# Sheet_2.net
KiCad netlist of a schematic drawn in Altium Designer
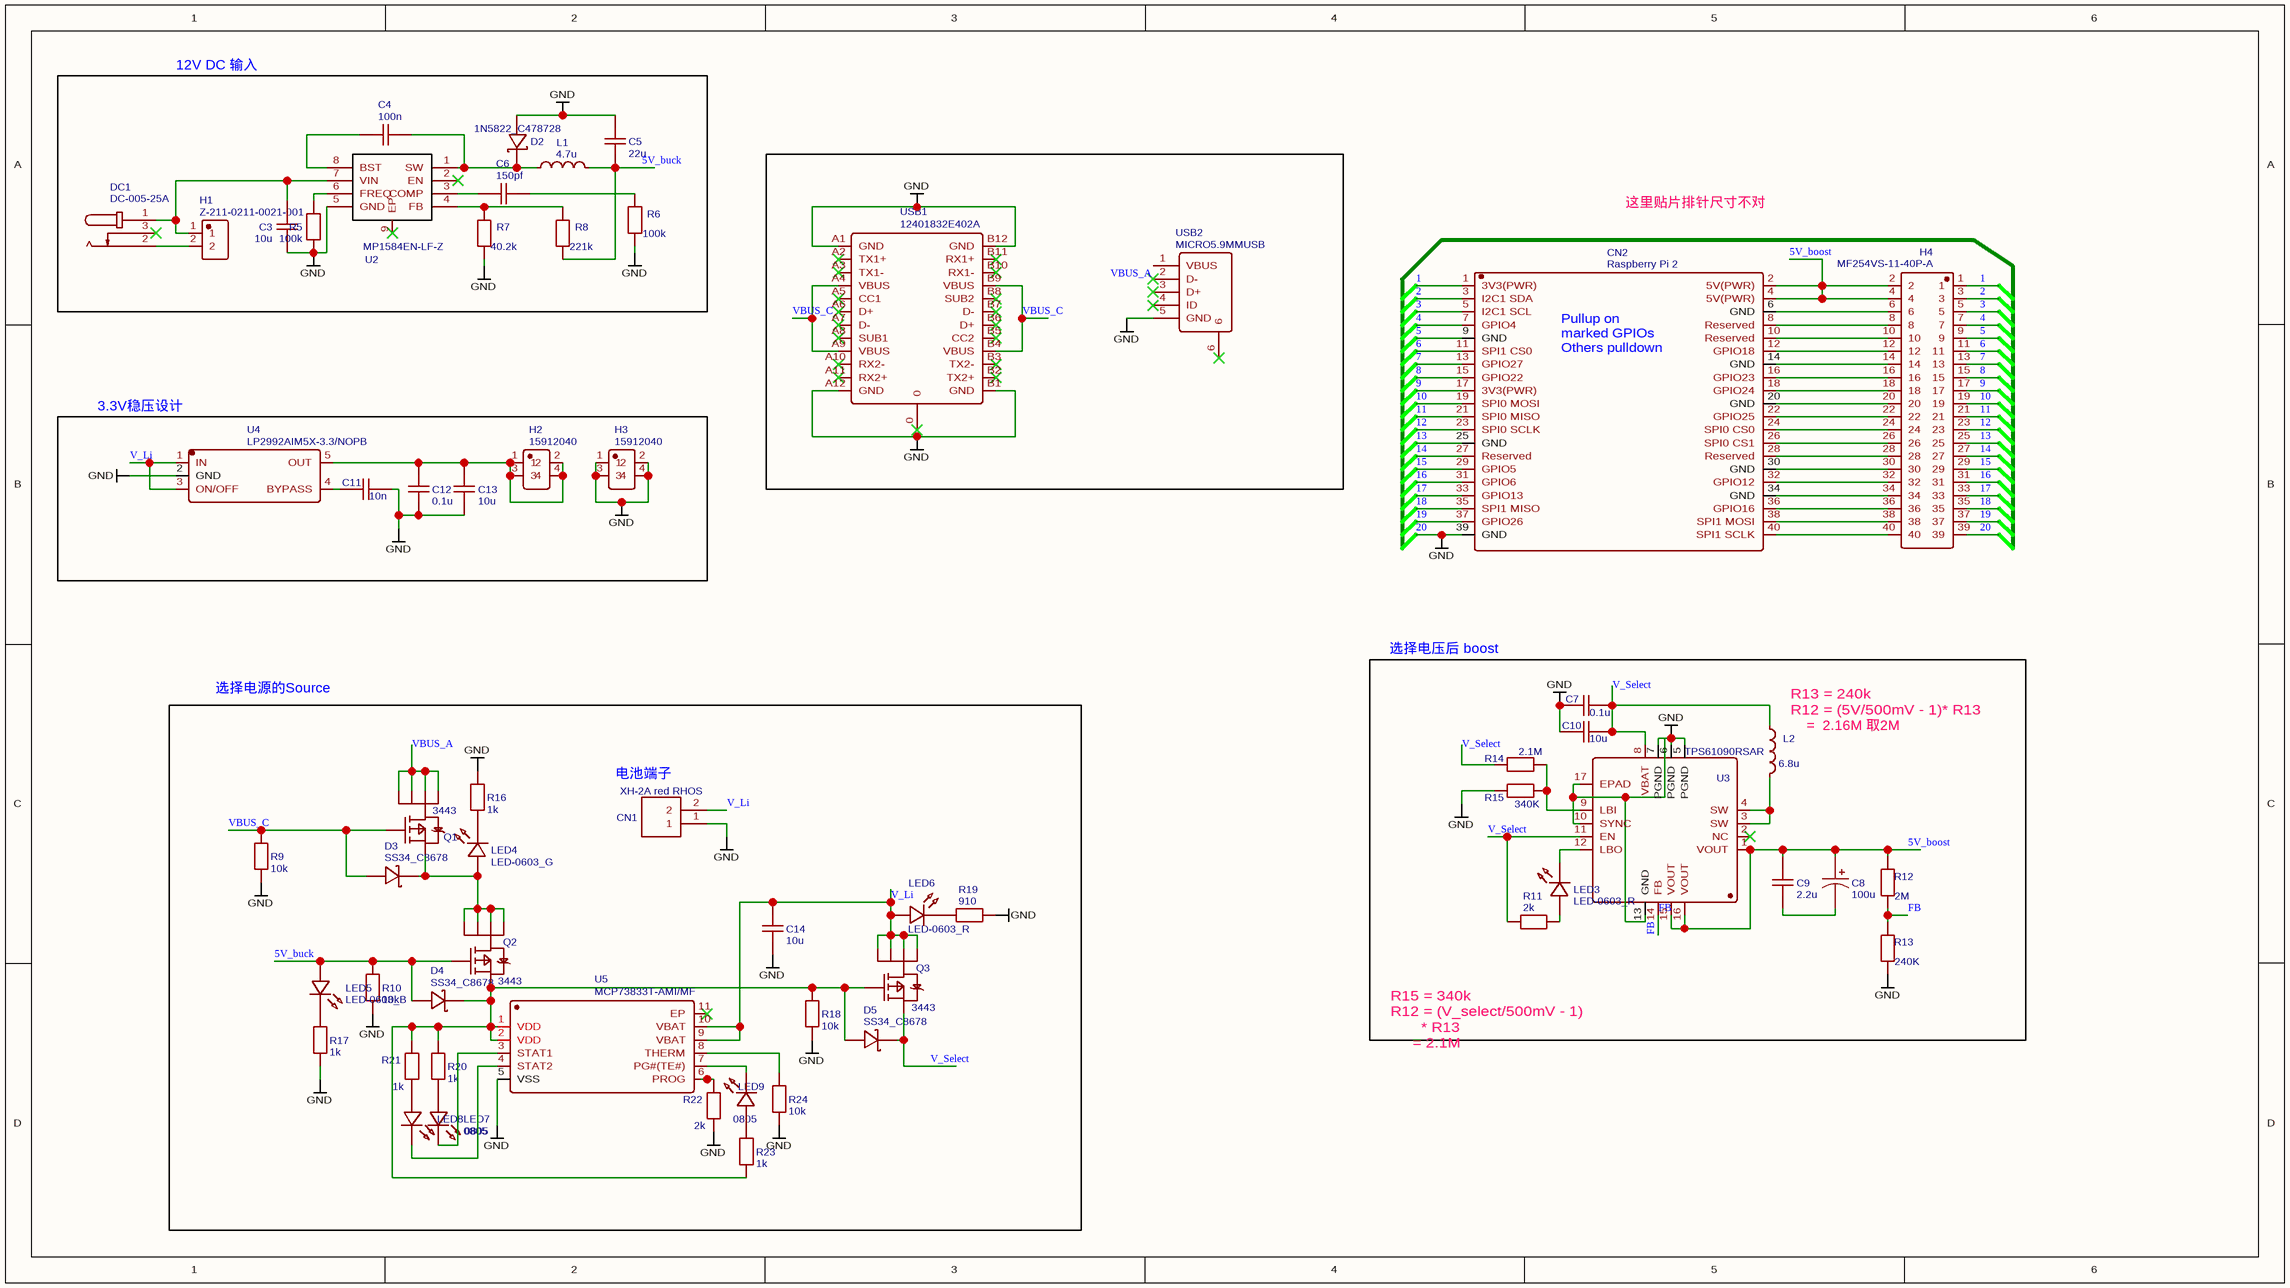
[diagram p0: Sheet_2.schdoc]

(export (version "E")
  (design (tool "Eeschema 10.0.6"))
  (components
    (comp (ref "C3")
      (value "10u")
      (fields (field (name "CONTRIBUTOR") "LCEDA_Lib"))
      (libsource (lib "altium-import") (part "root_1_10u_"))
    )
    (comp (ref "C4")
      (value "100n")
      (fields (field (name "CONTRIBUTOR") "LCEDA_Lib"))
      (libsource (lib "altium-import") (part "root_2_100n_"))
    )
    (comp (ref "C5")
      (value "22u")
      (fields (field (name "CONTRIBUTOR") "LCEDA_Lib"))
      (libsource (lib "altium-import") (part "root_3_22u_"))
    )
    (comp (ref "C6")
      (value "150pf")
      (fields (field (name "CONTRIBUTOR") "LCEDA_Lib"))
      (libsource (lib "altium-import") (part "root_0_150pf_"))
    )
    (comp (ref "C7")
      (value "0.1u")
      (fields (field (name "CONTRIBUTOR") "LCEDA_Lib"))
      (libsource (lib "altium-import") (part "root_2_0.1u_"))
    )
    (comp (ref "C8")
      (value "100u")
      (fields (field (name "CONTRIBUTOR") "LCEDA_Lib"))
      (libsource (lib "altium-import") (part "root_3_100u_"))
    )
    (comp (ref "C9")
      (value "2.2u")
      (fields (field (name "CONTRIBUTOR") "LCEDA_Lib"))
      (libsource (lib "altium-import") (part "root_1_2.2u_"))
    )
    (comp (ref "C10")
      (value "10u")
      (fields (field (name "CONTRIBUTOR") "LCEDA_Lib"))
      (libsource (lib "altium-import") (part "root_2_10u_"))
    )
    (comp (ref "C11")
      (value "10n")
      (fields (field (name "CONTRIBUTOR") "LCEDA_Lib"))
      (libsource (lib "altium-import") (part "root_2_10n_"))
    )
    (comp (ref "C12")
      (value "0.1u")
      (fields (field (name "CONTRIBUTOR") "LCEDA_Lib"))
      (libsource (lib "altium-import") (part "root_3_0.1u_"))
    )
    (comp (ref "C13")
      (value "10u")
      (fields (field (name "CONTRIBUTOR") "LCEDA_Lib"))
      (libsource (lib "altium-import") (part "root_3_10u_"))
    )
    (comp (ref "C14")
      (value "10u")
      (fields (field (name "CONTRIBUTOR") "LCEDA_Lib"))
      (libsource (lib "") (part "root_1_10u__1"))
    )
    (comp (ref "CN1")
      (value "XH-2A red RHOS")
      (fields (field (name "BOM_SUPPLIER PART") "C24192"))
      (libsource (lib "altium-import") (part "root_2_XH-2A red RHOS_"))
    )
    (comp (ref "CN2")
      (value "Raspberry Pi 2")
      (fields (field (name "CONTRIBUTOR") "Jason+Pierce"))
      (libsource (lib "altium-import") (part "root_0_Raspberry Pi 2_"))
    )
    (comp (ref "D2")
      (value "1N5822_C478728")
      (fields
        (field (name "BOM_SUPPLIER PART") "C478728")
        (field (name "BOM_MANUFACTURER PART") "1N5822")
        (field (name "CONTRIBUTOR") "LCSC")
      )
      (libsource (lib "altium-import") (part "root_1_1N5822_C478728_"))
    )
    (comp (ref "D3")
      (value "SS34_C8678")
      (fields (field (name "BOM_MANUFACTURER PART") "SS34") (field (name "BOM_SUPPLIER PART") "C8678"))
      (libsource (lib "altium-import") (part "root_2_SS34_C8678_"))
    )
    (comp (ref "D4")
      (value "SS34_C8678")
      (fields (field (name "BOM_MANUFACTURER PART") "SS34") (field (name "BOM_SUPPLIER PART") "C8678"))
      (libsource (lib "altium-import") (part "root_2_SS34_C8678_"))
    )
    (comp (ref "D5")
      (value "SS34_C8678")
      (fields (field (name "BOM_MANUFACTURER PART") "SS34") (field (name "BOM_SUPPLIER PART") "C8678"))
      (libsource (lib "altium-import") (part "root_2_SS34_C8678_"))
    )
    (comp (ref "DC1")
      (value "DC-005-25A")
      (fields (field (name "BOM_SUPPLIER PART") "C136715") (field (name "CONTRIBUTOR") "LCSC"))
      (libsource (lib "altium-import") (part "root_0_DC-005-25A_"))
    )
    (comp (ref "H1")
      (value "Z-211-0211-0021-001")
      (fields (field (name "BOM_SUPPLIER PART") "C152154") (field (name "CONTRIBUTOR") "LCSC"))
      (libsource (lib "altium-import") (part "root_0_Z-211-0211-0021-001_"))
    )
    (comp (ref "H2")
      (value "15912040")
      (fields (field (name "BOM_SUPPLIER PART") "C586564") (field (name "CONTRIBUTOR") "LCSC"))
      (libsource (lib "altium-import") (part "root_0_15912040_"))
    )
    (comp (ref "H3")
      (value "15912040")
      (fields (field (name "BOM_SUPPLIER PART") "C586564") (field (name "CONTRIBUTOR") "LCSC"))
      (libsource (lib "altium-import") (part "root_0_15912040_"))
    )
    (comp (ref "H4")
      (value "MF254VS-11-40P-A")
      (fields (field (name "BOM_SUPPLIER PART") "C492236") (field (name "CONTRIBUTOR") "LCSC"))
      (libsource (lib "altium-import") (part "root_0_MF254VS-11-40P-A_"))
    )
    (comp (ref "L1")
      (value "4.7u")
      (fields (field (name "CONTRIBUTOR") "LCEDA_Lib"))
      (libsource (lib "altium-import") (part "root_0_4.7u_"))
    )
    (comp (ref "L2")
      (value "6.8u")
      (fields (field (name "CONTRIBUTOR") "LCEDA_Lib"))
      (libsource (lib "altium-import") (part "root_3_6.8u_"))
    )
    (comp (ref "LED3")
      (value "LED-0603_R")
      (fields
        (field (name "BOM_MANUFACTURER PART") "19-217/R6C-AL1M2VY/3T")
        (field (name "BOM_SUPPLIER PART") "C72044")
        (field (name "CONTRIBUTOR") "LCEDA_01")
      )
      (libsource (lib "altium-import") (part "root_1_LED-0603_R_"))
    )
    (comp (ref "LED4")
      (value "LED-0603_G")
      (fields
        (field (name "BOM_MANUFACTURER PART") "19-217/GHC-YR1S2/3T")
        (field (name "BOM_SUPPLIER PART") "C72043")
        (field (name "CONTRIBUTOR") "LCEDA_Lib")
      )
      (libsource (lib "altium-import") (part "root_1_LED-0603_G_"))
    )
    (comp (ref "LED5")
      (value "LED-0603_B")
      (fields
        (field (name "BOM_MANUFACTURER PART") "19-217/BHC-ZL1M2RY/3T")
        (field (name "BOM_SUPPLIER PART") "C72041")
        (field (name "CONTRIBUTOR") "LCEDA_01")
      )
      (libsource (lib "altium-import") (part "root_3_LED-0603_B_"))
    )
    (comp (ref "LED6")
      (value "LED-0603_R")
      (fields
        (field (name "BOM_MANUFACTURER PART") "19-217/R6C-AL1M2VY/3T")
        (field (name "BOM_SUPPLIER PART") "C72044")
        (field (name "CONTRIBUTOR") "LCEDA_01")
      )
      (libsource (lib "altium-import") (part "root_0_LED-0603_R_"))
    )
    (comp (ref "LED7")
      (value "0805")
      (fields
        (field (name "BOM_MANUFACTURER PART") "17-21SURC/S530-A3/TR8")
        (field (name "BOM_SUPPLIER PART") "C72037")
        (field (name "CONTRIBUTOR") "LCEDA_Lib")
      )
      (libsource (lib "altium-import") (part "root_3_0805_"))
    )
    (comp (ref "LED8")
      (value "0805")
      (fields
        (field (name "BOM_MANUFACTURER PART") "NCD0805G1")
        (field (name "BOM_SUPPLIER PART") "C84260")
        (field (name "CONTRIBUTOR") "LCEDA_Lib")
      )
      (libsource (lib "altium-import") (part "root_3_0805_"))
    )
    (comp (ref "LED9")
      (value "0805")
      (fields
        (field (name "BOM_MANUFACTURER PART") "D-B080508B1-KS2")
        (field (name "BOM_SUPPLIER PART") "C108412")
        (field (name "CONTRIBUTOR") "LCEDA_Lib")
      )
      (libsource (lib "altium-import") (part "root_1_0805_"))
    )
    (comp (ref "Q1")
      (value "3443")
      (fields
        (field (name "BOM_SUPPLIER PART") "C558216")
        (field (name "BOM_MANUFACTURER PART") "NTGS3443T1G")
        (field (name "CONTRIBUTOR") "LCSC")
      )
      (libsource (lib "altium-import") (part "root_2_3443_"))
    )
    (comp (ref "Q2")
      (value "3443")
      (fields
        (field (name "BOM_SUPPLIER PART") "C558216")
        (field (name "BOM_MANUFACTURER PART") "NTGS3443T1G")
        (field (name "CONTRIBUTOR") "LCSC")
      )
      (libsource (lib "altium-import") (part "root_2_3443_"))
    )
    (comp (ref "Q3")
      (value "3443")
      (fields
        (field (name "BOM_SUPPLIER PART") "C558216")
        (field (name "BOM_MANUFACTURER PART") "NTGS3443T1G")
        (field (name "CONTRIBUTOR") "LCSC")
      )
      (libsource (lib "altium-import") (part "root_2_3443_"))
    )
    (comp (ref "R5")
      (value "100k")
      (fields (field (name "CONTRIBUTOR") "LCEDA_Lib"))
      (libsource (lib "altium-import") (part "root_3_100k_"))
    )
    (comp (ref "R6")
      (value "100k")
      (fields (field (name "CONTRIBUTOR") "LCEDA_Lib"))
      (libsource (lib "altium-import") (part "root_3_100k_"))
    )
    (comp (ref "R7")
      (value "40.2k")
      (fields (field (name "CONTRIBUTOR") "LCEDA_Lib"))
      (libsource (lib "altium-import") (part "root_3_40.2k_"))
    )
    (comp (ref "R8")
      (value "221k")
      (fields (field (name "CONTRIBUTOR") "LCEDA_Lib"))
      (libsource (lib "altium-import") (part "root_3_221k_"))
    )
    (comp (ref "R9")
      (value "10k")
      (fields (field (name "CONTRIBUTOR") "LCEDA_Lib"))
      (libsource (lib "altium-import") (part "root_1_10k_"))
    )
    (comp (ref "R10")
      (value "10k")
      (fields (field (name "CONTRIBUTOR") "LCEDA_Lib"))
      (libsource (lib "altium-import") (part "root_1_10k_"))
    )
    (comp (ref "R11")
      (value "2k")
      (fields (field (name "CONTRIBUTOR") "LCEDA_Lib"))
      (libsource (lib "altium-import") (part "root_2_2k_"))
    )
    (comp (ref "R12")
      (value "2M")
      (fields (field (name "CONTRIBUTOR") "LCEDA_Lib"))
      (libsource (lib "altium-import") (part "root_3_2M_"))
    )
    (comp (ref "R13")
      (value "240K")
      (fields (field (name "CONTRIBUTOR") "LCEDA_Lib"))
      (libsource (lib "altium-import") (part "root_3_240K_"))
    )
    (comp (ref "R14")
      (value "2.1M")
      (fields (field (name "CONTRIBUTOR") "LCEDA_Lib"))
      (libsource (lib "altium-import") (part "root_2_2.1M_"))
    )
    (comp (ref "R15")
      (value "340K")
      (fields (field (name "CONTRIBUTOR") "LCEDA_Lib"))
      (libsource (lib "altium-import") (part "root_2_340K_"))
    )
    (comp (ref "R16")
      (value "1k")
      (fields (field (name "CONTRIBUTOR") "LCEDA_Lib"))
      (libsource (lib "altium-import") (part "root_1_1k_"))
    )
    (comp (ref "R17")
      (value "1k")
      (fields (field (name "CONTRIBUTOR") "LCEDA_Lib"))
      (libsource (lib "altium-import") (part "root_1_1k_"))
    )
    (comp (ref "R18")
      (value "10k")
      (fields (field (name "CONTRIBUTOR") "LCEDA_Lib"))
      (libsource (lib "altium-import") (part "root_1_10k_"))
    )
    (comp (ref "R19")
      (value "910")
      (fields (field (name "CONTRIBUTOR") "LCEDA_Lib"))
      (libsource (lib "altium-import") (part "root_2_910_"))
    )
    (comp (ref "R20")
      (value "1k")
      (fields (field (name "CONTRIBUTOR") "LCEDA_Lib"))
      (libsource (lib "altium-import") (part "root_1_1k_"))
    )
    (comp (ref "R21")
      (value "1k")
      (fields (field (name "CONTRIBUTOR") "LCEDA_Lib"))
      (libsource (lib "altium-import") (part "root_1_1k_"))
    )
    (comp (ref "R22")
      (value "2k")
      (fields (field (name "CONTRIBUTOR") "LCEDA_Lib"))
      (libsource (lib "altium-import") (part "root_1_2k_"))
    )
    (comp (ref "R23")
      (value "1k")
      (fields (field (name "CONTRIBUTOR") "LCEDA_Lib"))
      (libsource (lib "altium-import") (part "root_1_1k_"))
    )
    (comp (ref "R24")
      (value "10k")
      (fields (field (name "CONTRIBUTOR") "LCEDA_Lib"))
      (libsource (lib "altium-import") (part "root_1_10k_"))
    )
    (comp (ref "U2")
      (value "MP1584EN-LF-Z")
      (fields (field (name "BOM_SUPPLIER PART") "C15051"))
      (libsource (lib "altium-import") (part "root_0_MP1584EN-LF-Z_"))
    )
    (comp (ref "U3")
      (value "TPS61090RSAR")
      (fields (field (name "BOM_SUPPLIER PART") "C206167") (field (name "CONTRIBUTOR") "LCSC"))
      (libsource (lib "altium-import") (part "root_2_TPS61090RSAR_"))
    )
    (comp (ref "U4")
      (value "LP2992AIM5X-3.3/NOPB")
      (fields (field (name "BOM_SUPPLIER PART") "C111076") (field (name "CONTRIBUTOR") "LCSC"))
      (libsource (lib "altium-import") (part "root_0_LP2992AIM5X-3.3/NOPB_"))
    )
    (comp (ref "U5")
      (value "MCP73833T-AMI/MF")
      (fields (field (name "BOM_SUPPLIER PART") "C340160") (field (name "CONTRIBUTOR") "LCSC"))
      (libsource (lib "altium-import") (part "root_0_MCP73833T-AMI/MF_"))
    )
    (comp (ref "USB1")
      (value "12401832E402A")
      (fields (field (name "BOM_SUPPLIER PART") "C464604") (field (name "CONTRIBUTOR") "LCSC"))
      (libsource (lib "altium-import") (part "root_0_12401832E402A_"))
    )
    (comp (ref "USB2")
      (value "MICRO5.9MMUSB")
      (fields
        (field (name "BOM_SUPPLIER PART") "C393940")
        (field (name "BOM_MANUFACTURER PART") "MICRO5.9mmusb")
        (field (name "CONTRIBUTOR") "LCSC")
      )
      (libsource (lib "altium-import") (part "root_0_MICRO5.9MMUSB_"))
    )
  )
  (nets
    (net (code "1") (name "/1") (class "Default")
      (node (ref "CN2") (pin "1") (pinfunction "3V3(PWR)_1") (pintype "passive"))
      (node (ref "H4") (pin "1") (pinfunction "1_1") (pintype "passive"))
    )
    (net (code "2") (name "/2") (class "Default")
      (node (ref "CN2") (pin "3") (pinfunction "I2C1_SDA_3") (pintype "passive"))
      (node (ref "H4") (pin "3") (pinfunction "3_3") (pintype "passive"))
    )
    (net (code "3") (name "/3") (class "Default")
      (node (ref "CN2") (pin "5") (pinfunction "I2C1_SCL_5") (pintype "passive"))
      (node (ref "H4") (pin "5") (pinfunction "5_5") (pintype "passive"))
    )
    (net (code "4") (name "/4") (class "Default")
      (node (ref "CN2") (pin "7") (pinfunction "GPIO4_7") (pintype "passive"))
      (node (ref "H4") (pin "7") (pinfunction "7_7") (pintype "passive"))
    )
    (net (code "5") (name "/5") (class "Default")
      (node (ref "CN2") (pin "9") (pinfunction "GND_9") (pintype "passive"))
      (node (ref "H4") (pin "9") (pinfunction "9_9") (pintype "passive"))
    )
    (net (code "6") (name "/5V_boost") (class "Default")
      (node (ref "C8") (pin "1") (pinfunction "1_1") (pintype "passive"))
      (node (ref "C9") (pin "2") (pinfunction "2_2") (pintype "passive"))
      (node (ref "CN2") (pin "2") (pinfunction "5V(PWR)_2") (pintype "passive"))
      (node (ref "CN2") (pin "4") (pinfunction "5V(PWR)_4") (pintype "passive"))
      (node (ref "H4") (pin "2") (pinfunction "2_2") (pintype "passive"))
      (node (ref "H4") (pin "4") (pinfunction "4_4") (pintype "passive"))
      (node (ref "R12") (pin "1") (pinfunction "1_1") (pintype "passive"))
      (node (ref "U3") (pin "1") (pinfunction "VOUT_1") (pintype "passive"))
      (node (ref "U3") (pin "15") (pinfunction "VOUT_15") (pintype "passive"))
      (node (ref "U3") (pin "16") (pinfunction "VOUT_16") (pintype "passive"))
    )
    (net (code "7") (name "/5V_buck") (class "Default")
      (node (ref "C5") (pin "2") (pinfunction "2_2") (pintype "passive"))
      (node (ref "D4") (pin "2") (pinfunction "A_2") (pintype "passive"))
      (node (ref "L1") (pin "2") (pinfunction "2_2") (pintype "passive"))
      (node (ref "LED5") (pin "1") (pinfunction "1_1") (pintype "passive"))
      (node (ref "Q2") (pin "3") (pinfunction "G_3") (pintype "passive"))
      (node (ref "R10") (pin "2") (pinfunction "2_2") (pintype "passive"))
      (node (ref "R8") (pin "2") (pinfunction "2_2") (pintype "passive"))
    )
    (net (code "8") (name "/6") (class "Default")
      (node (ref "CN2") (pin "11") (pinfunction "SPI1_CS0_11") (pintype "passive"))
      (node (ref "H4") (pin "11") (pinfunction "11_11") (pintype "passive"))
    )
    (net (code "9") (name "/7") (class "Default")
      (node (ref "CN2") (pin "13") (pinfunction "GPIO27_13") (pintype "passive"))
      (node (ref "H4") (pin "13") (pinfunction "13_13") (pintype "passive"))
    )
    (net (code "10") (name "/8") (class "Default")
      (node (ref "CN2") (pin "15") (pinfunction "GPIO22_15") (pintype "passive"))
      (node (ref "H4") (pin "15") (pinfunction "15_15") (pintype "passive"))
    )
    (net (code "11") (name "/9") (class "Default")
      (node (ref "CN2") (pin "17") (pinfunction "3V3(PWR)_17") (pintype "passive"))
      (node (ref "H4") (pin "17") (pinfunction "17_17") (pintype "passive"))
    )
    (net (code "12") (name "/10") (class "Default")
      (node (ref "CN2") (pin "19") (pinfunction "SPI0_MOSI_19") (pintype "passive"))
      (node (ref "H4") (pin "19") (pinfunction "19_19") (pintype "passive"))
    )
    (net (code "13") (name "/11") (class "Default")
      (node (ref "CN2") (pin "21") (pinfunction "SPI0_MISO_21") (pintype "passive"))
      (node (ref "H4") (pin "21") (pinfunction "21_21") (pintype "passive"))
    )
    (net (code "14") (name "/12") (class "Default")
      (node (ref "CN2") (pin "23") (pinfunction "SPI0_SCLK_23") (pintype "passive"))
      (node (ref "H4") (pin "23") (pinfunction "23_23") (pintype "passive"))
    )
    (net (code "15") (name "/13") (class "Default")
      (node (ref "CN2") (pin "25") (pinfunction "GND_25") (pintype "passive"))
      (node (ref "H4") (pin "25") (pinfunction "25_25") (pintype "passive"))
    )
    (net (code "16") (name "/14") (class "Default")
      (node (ref "CN2") (pin "27") (pinfunction "Reserved_27") (pintype "passive"))
      (node (ref "H4") (pin "27") (pinfunction "27_27") (pintype "passive"))
    )
    (net (code "17") (name "/15") (class "Default")
      (node (ref "CN2") (pin "29") (pinfunction "GPIO5_29") (pintype "passive"))
      (node (ref "H4") (pin "29") (pinfunction "29_29") (pintype "passive"))
    )
    (net (code "18") (name "/16") (class "Default")
      (node (ref "CN2") (pin "31") (pinfunction "GPIO6_31") (pintype "passive"))
      (node (ref "H4") (pin "31") (pinfunction "31_31") (pintype "passive"))
    )
    (net (code "19") (name "/17") (class "Default")
      (node (ref "CN2") (pin "33") (pinfunction "GPIO13_33") (pintype "passive"))
      (node (ref "H4") (pin "33") (pinfunction "33_33") (pintype "passive"))
    )
    (net (code "20") (name "/18") (class "Default")
      (node (ref "CN2") (pin "35") (pinfunction "SPI1_MISO_35") (pintype "passive"))
      (node (ref "H4") (pin "35") (pinfunction "35_35") (pintype "passive"))
    )
    (net (code "21") (name "/19") (class "Default")
      (node (ref "CN2") (pin "37") (pinfunction "GPIO26_37") (pintype "passive"))
      (node (ref "H4") (pin "37") (pinfunction "37_37") (pintype "passive"))
    )
    (net (code "22") (name "/FB") (class "Default")
      (node (ref "R12") (pin "2") (pinfunction "2_2") (pintype "passive"))
      (node (ref "R13") (pin "1") (pinfunction "1_1") (pintype "passive"))
      (node (ref "U3") (pin "14") (pinfunction "FB_14") (pintype "passive"))
    )
    (net (code "23") (name "/VBUS_A") (class "Default")
      (node (ref "Q1") (pin "1") (pinfunction "D_1") (pintype "passive"))
      (node (ref "Q1") (pin "2") (pinfunction "D_2") (pintype "passive"))
      (node (ref "Q1") (pin "5") (pinfunction "D_5") (pintype "passive"))
      (node (ref "Q1") (pin "6") (pinfunction "D_6") (pintype "passive"))
      (node (ref "USB2") (pin "1") (pinfunction "VBUS_1") (pintype "passive"))
    )
    (net (code "24") (name "/VBUS_C") (class "Default")
      (node (ref "D3") (pin "2") (pinfunction "A_2") (pintype "passive"))
      (node (ref "Q1") (pin "3") (pinfunction "G_3") (pintype "passive"))
      (node (ref "R9") (pin "2") (pinfunction "2_2") (pintype "passive"))
      (node (ref "USB1") (pin "A4") (pinfunction "VBUS_A4") (pintype "passive"))
      (node (ref "USB1") (pin "A9") (pinfunction "VBUS_A9") (pintype "passive"))
      (node (ref "USB1") (pin "B4") (pinfunction "VBUS_B4") (pintype "passive"))
      (node (ref "USB1") (pin "B9") (pinfunction "VBUS_B9") (pintype "passive"))
    )
    (net (code "25") (name "/V_Li") (class "Default")
      (node (ref "C14") (pin "2") (pinfunction "2_2") (pintype "passive"))
      (node (ref "CN1") (pin "2") (pinfunction "2_2") (pintype "passive"))
      (node (ref "LED6") (pin "1") (pinfunction "1_1") (pintype "passive"))
      (node (ref "Q3") (pin "1") (pinfunction "D_1") (pintype "passive"))
      (node (ref "Q3") (pin "2") (pinfunction "D_2") (pintype "passive"))
      (node (ref "Q3") (pin "5") (pinfunction "D_5") (pintype "passive"))
      (node (ref "Q3") (pin "6") (pinfunction "D_6") (pintype "passive"))
      (node (ref "U4") (pin "1") (pinfunction "IN_1") (pintype "passive"))
      (node (ref "U4") (pin "3") (pinfunction "ON/OFF_3") (pintype "passive"))
      (node (ref "U5") (pin "10") (pinfunction "VBAT_10") (pintype "passive"))
      (node (ref "U5") (pin "9") (pinfunction "VBAT_9") (pintype "passive"))
    )
    (net (code "26") (name "/V_Select") (class "Default")
      (node (ref "C10") (pin "1") (pinfunction "1_1") (pintype "passive"))
      (node (ref "C7") (pin "1") (pinfunction "1_1") (pintype "passive"))
      (node (ref "D5") (pin "1") (pinfunction "K_1") (pintype "passive"))
      (node (ref "L2") (pin "1") (pinfunction "1_1") (pintype "passive"))
      (node (ref "Q3") (pin "4") (pinfunction "S_4") (pintype "passive"))
      (node (ref "R11") (pin "2") (pinfunction "2_2") (pintype "passive"))
      (node (ref "R14") (pin "2") (pinfunction "2_2") (pintype "passive"))
      (node (ref "U3") (pin "11") (pinfunction "EN_11") (pintype "passive"))
      (node (ref "U3") (pin "8") (pinfunction "VBAT_8") (pintype "passive"))
    )
    (net (code "27") (name "GND") (class "Default")
      (node (ref "C10") (pin "2") (pinfunction "2_2") (pintype "passive"))
      (node (ref "C11") (pin "1") (pinfunction "1_1") (pintype "passive"))
      (node (ref "C12") (pin "2") (pinfunction "2_2") (pintype "passive"))
      (node (ref "C13") (pin "2") (pinfunction "2_2") (pintype "passive"))
      (node (ref "C14") (pin "1") (pinfunction "1_1") (pintype "passive"))
      (node (ref "C3") (pin "1") (pinfunction "1_1") (pintype "passive"))
      (node (ref "C5") (pin "1") (pinfunction "1_1") (pintype "passive"))
      (node (ref "C7") (pin "2") (pinfunction "2_2") (pintype "passive"))
      (node (ref "CN1") (pin "1") (pinfunction "1_1") (pintype "passive"))
      (node (ref "CN2") (pin "39") (pinfunction "GND_39") (pintype "passive"))
      (node (ref "D2") (pin "2") (pinfunction "A_2") (pintype "passive"))
      (node (ref "H3") (pin "1") (pinfunction "1_1") (pintype "passive"))
      (node (ref "H3") (pin "2") (pinfunction "2_2") (pintype "passive"))
      (node (ref "H3") (pin "3") (pinfunction "3_3") (pintype "passive"))
      (node (ref "H3") (pin "4") (pinfunction "4_4") (pintype "passive"))
      (node (ref "H4") (pin "39") (pinfunction "39_39") (pintype "passive"))
      (node (ref "R10") (pin "1") (pinfunction "1_1") (pintype "passive"))
      (node (ref "R13") (pin "2") (pinfunction "2_2") (pintype "passive"))
      (node (ref "R15") (pin "2") (pinfunction "2_2") (pintype "passive"))
      (node (ref "R16") (pin "2") (pinfunction "2_2") (pintype "passive"))
      (node (ref "R17") (pin "1") (pinfunction "1_1") (pintype "passive"))
      (node (ref "R18") (pin "1") (pinfunction "1_1") (pintype "passive"))
      (node (ref "R19") (pin "1") (pinfunction "1_1") (pintype "passive"))
      (node (ref "R22") (pin "1") (pinfunction "1_1") (pintype "passive"))
      (node (ref "R24") (pin "1") (pinfunction "1_1") (pintype "passive"))
      (node (ref "R5") (pin "2") (pinfunction "2_2") (pintype "passive"))
      (node (ref "R6") (pin "2") (pinfunction "2_2") (pintype "passive"))
      (node (ref "R7") (pin "2") (pinfunction "2_2") (pintype "passive"))
      (node (ref "R9") (pin "1") (pinfunction "1_1") (pintype "passive"))
      (node (ref "U2") (pin "5") (pinfunction "GND_5") (pintype "passive"))
      (node (ref "U3") (pin "10") (pinfunction "SYNC_10") (pintype "passive"))
      (node (ref "U3") (pin "13") (pinfunction "GND_13") (pintype "passive"))
      (node (ref "U3") (pin "17") (pinfunction "EPAD_17") (pintype "passive"))
      (node (ref "U3") (pin "5") (pinfunction "PGND_5") (pintype "passive"))
      (node (ref "U3") (pin "6") (pinfunction "PGND_6") (pintype "passive"))
      (node (ref "U3") (pin "7") (pinfunction "PGND_7") (pintype "passive"))
      (node (ref "U4") (pin "2") (pinfunction "GND_2") (pintype "passive"))
      (node (ref "U5") (pin "5") (pinfunction "VSS_5") (pintype "passive"))
      (node (ref "USB1") (pin "A1") (pinfunction "GND_A1") (pintype "passive"))
      (node (ref "USB1") (pin "A12") (pinfunction "GND_A12") (pintype "passive"))
      (node (ref "USB1") (pin "B1") (pinfunction "GND_B1") (pintype "passive"))
      (node (ref "USB1") (pin "B12") (pinfunction "GND_B12") (pintype "passive"))
      (node (ref "USB2") (pin "5") (pinfunction "GND_5") (pintype "passive"))
    )
    (net (code "28") (name "Net-(C6-Pad2)") (class "Default")
      (node (ref "C6") (pin "2") (pinfunction "2_2") (pintype "passive"))
      (node (ref "R6") (pin "1") (pinfunction "1_1") (pintype "passive"))
    )
    (net (code "29") (name "Net-(C8-Pad2)") (class "Default")
      (node (ref "C8") (pin "2") (pinfunction "2_2") (pintype "passive"))
      (node (ref "C9") (pin "1") (pinfunction "1_1") (pintype "passive"))
    )
    (net (code "30") (name "Net-(CN2-GND-Pad6)") (class "Default")
      (node (ref "CN2") (pin "6") (pinfunction "GND_6") (pintype "passive"))
      (node (ref "H4") (pin "6") (pinfunction "6_6") (pintype "passive"))
    )
    (net (code "31") (name "Net-(CN2-GND-Pad14)") (class "Default")
      (node (ref "CN2") (pin "14") (pinfunction "GND_14") (pintype "passive"))
      (node (ref "H4") (pin "14") (pinfunction "14_14") (pintype "passive"))
    )
    (net (code "32") (name "Net-(CN2-GND-Pad20)") (class "Default")
      (node (ref "CN2") (pin "20") (pinfunction "GND_20") (pintype "passive"))
      (node (ref "H4") (pin "20") (pinfunction "20_20") (pintype "passive"))
    )
    (net (code "33") (name "Net-(CN2-GND-Pad30)") (class "Default")
      (node (ref "CN2") (pin "30") (pinfunction "GND_30") (pintype "passive"))
      (node (ref "H4") (pin "30") (pinfunction "30_30") (pintype "passive"))
    )
    (net (code "34") (name "Net-(CN2-GND-Pad34)") (class "Default")
      (node (ref "CN2") (pin "34") (pinfunction "GND_34") (pintype "passive"))
      (node (ref "H4") (pin "34") (pinfunction "34_34") (pintype "passive"))
    )
    (net (code "35") (name "Net-(CN2-GPIO12)") (class "Default")
      (node (ref "CN2") (pin "32") (pinfunction "GPIO12_32") (pintype "passive"))
      (node (ref "H4") (pin "32") (pinfunction "32_32") (pintype "passive"))
    )
    (net (code "36") (name "Net-(CN2-GPIO16)") (class "Default")
      (node (ref "CN2") (pin "36") (pinfunction "GPIO16_36") (pintype "passive"))
      (node (ref "H4") (pin "36") (pinfunction "36_36") (pintype "passive"))
    )
    (net (code "37") (name "Net-(CN2-GPIO18)") (class "Default")
      (node (ref "CN2") (pin "12") (pinfunction "GPIO18_12") (pintype "passive"))
      (node (ref "H4") (pin "12") (pinfunction "12_12") (pintype "passive"))
    )
    (net (code "38") (name "Net-(CN2-GPIO23)") (class "Default")
      (node (ref "CN2") (pin "16") (pinfunction "GPIO23_16") (pintype "passive"))
      (node (ref "H4") (pin "16") (pinfunction "16_16") (pintype "passive"))
    )
    (net (code "39") (name "Net-(CN2-GPIO24)") (class "Default")
      (node (ref "CN2") (pin "18") (pinfunction "GPIO24_18") (pintype "passive"))
      (node (ref "H4") (pin "18") (pinfunction "18_18") (pintype "passive"))
    )
    (net (code "40") (name "Net-(CN2-GPIO25)") (class "Default")
      (node (ref "CN2") (pin "22") (pinfunction "GPIO25_22") (pintype "passive"))
      (node (ref "H4") (pin "22") (pinfunction "22_22") (pintype "passive"))
    )
    (net (code "41") (name "Net-(CN2-Reserved-Pad8)") (class "Default")
      (node (ref "CN2") (pin "8") (pinfunction "Reserved_8") (pintype "passive"))
      (node (ref "H4") (pin "8") (pinfunction "8_8") (pintype "passive"))
    )
    (net (code "42") (name "Net-(CN2-Reserved-Pad10)") (class "Default")
      (node (ref "CN2") (pin "10") (pinfunction "Reserved_10") (pintype "passive"))
      (node (ref "H4") (pin "10") (pinfunction "10_10") (pintype "passive"))
    )
    (net (code "43") (name "Net-(CN2-Reserved-Pad28)") (class "Default")
      (node (ref "CN2") (pin "28") (pinfunction "Reserved_28") (pintype "passive"))
      (node (ref "H4") (pin "28") (pinfunction "28_28") (pintype "passive"))
    )
    (net (code "44") (name "Net-(CN2-SPI0_CS0)") (class "Default")
      (node (ref "CN2") (pin "24") (pinfunction "SPI0_CS0_24") (pintype "passive"))
      (node (ref "H4") (pin "24") (pinfunction "24_24") (pintype "passive"))
    )
    (net (code "45") (name "Net-(CN2-SPI0_CS1)") (class "Default")
      (node (ref "CN2") (pin "26") (pinfunction "SPI0_CS1_26") (pintype "passive"))
      (node (ref "H4") (pin "26") (pinfunction "26_26") (pintype "passive"))
    )
    (net (code "46") (name "Net-(CN2-SPI1_MOSI)") (class "Default")
      (node (ref "CN2") (pin "38") (pinfunction "SPI1_MOSI_38") (pintype "passive"))
      (node (ref "H4") (pin "38") (pinfunction "38_38") (pintype "passive"))
    )
    (net (code "47") (name "Net-(CN2-SPI1_SCLK)") (class "Default")
      (node (ref "CN2") (pin "40") (pinfunction "SPI1_SCLK_40") (pintype "passive"))
      (node (ref "H4") (pin "40") (pinfunction "40_40") (pintype "passive"))
    )
    (net (code "48") (name "Net-(D2-K)") (class "Default")
      (node (ref "C4") (pin "1") (pinfunction "1_1") (pintype "passive"))
      (node (ref "D2") (pin "1") (pinfunction "K_1") (pintype "passive"))
      (node (ref "L1") (pin "1") (pinfunction "1_1") (pintype "passive"))
      (node (ref "U2") (pin "1") (pinfunction "SW_1") (pintype "passive"))
    )
    (net (code "49") (name "Net-(D3-K)") (class "Default")
      (node (ref "D3") (pin "1") (pinfunction "K_1") (pintype "passive"))
      (node (ref "LED4") (pin "1") (pinfunction "1_1") (pintype "passive"))
      (node (ref "Q1") (pin "4") (pinfunction "S_4") (pintype "passive"))
      (node (ref "Q2") (pin "1") (pinfunction "D_1") (pintype "passive"))
      (node (ref "Q2") (pin "2") (pinfunction "D_2") (pintype "passive"))
      (node (ref "Q2") (pin "5") (pinfunction "D_5") (pintype "passive"))
      (node (ref "Q2") (pin "6") (pinfunction "D_6") (pintype "passive"))
    )
    (net (code "50") (name "Net-(D4-K)") (class "Default")
      (node (ref "D4") (pin "1") (pinfunction "K_1") (pintype "passive"))
      (node (ref "D5") (pin "2") (pinfunction "A_2") (pintype "passive"))
      (node (ref "Q2") (pin "4") (pinfunction "S_4") (pintype "passive"))
      (node (ref "Q3") (pin "3") (pinfunction "G_3") (pintype "passive"))
      (node (ref "R18") (pin "2") (pinfunction "2_2") (pintype "passive"))
      (node (ref "R20") (pin "2") (pinfunction "2_2") (pintype "passive"))
      (node (ref "R21") (pin "2") (pinfunction "2_2") (pintype "passive"))
      (node (ref "R23") (pin "1") (pinfunction "1_1") (pintype "passive"))
      (node (ref "U5") (pin "1") (pinfunction "VDD_1") (pintype "passive"))
      (node (ref "U5") (pin "2") (pinfunction "VDD_2") (pintype "passive"))
    )
    (net (code "51") (name "Net-(DC1-Pad2)") (class "Default")
      (node (ref "DC1") (pin "2") (pinfunction "2_2") (pintype "passive"))
      (node (ref "H1") (pin "2") (pinfunction "2_2") (pintype "passive"))
    )
    (net (code "52") (name "Net-(L2-Pad2)") (class "Default")
      (node (ref "L2") (pin "2") (pinfunction "2_2") (pintype "passive"))
      (node (ref "U3") (pin "3") (pinfunction "SW_3") (pintype "passive"))
      (node (ref "U3") (pin "4") (pinfunction "SW_4") (pintype "passive"))
    )
    (net (code "53") (name "Net-(LED3-Pad1)") (class "Default")
      (node (ref "LED3") (pin "1") (pinfunction "1_1") (pintype "passive"))
      (node (ref "R11") (pin "1") (pinfunction "1_1") (pintype "passive"))
    )
    (net (code "54") (name "Net-(LED4-Pad2)") (class "Default")
      (node (ref "LED4") (pin "2") (pinfunction "2_2") (pintype "passive"))
      (node (ref "R16") (pin "1") (pinfunction "1_1") (pintype "passive"))
    )
    (net (code "55") (name "Net-(LED5-Pad2)") (class "Default")
      (node (ref "LED5") (pin "2") (pinfunction "2_2") (pintype "passive"))
      (node (ref "R17") (pin "2") (pinfunction "2_2") (pintype "passive"))
    )
    (net (code "56") (name "Net-(LED6-Pad2)") (class "Default")
      (node (ref "LED6") (pin "2") (pinfunction "2_2") (pintype "passive"))
      (node (ref "R19") (pin "2") (pinfunction "2_2") (pintype "passive"))
    )
    (net (code "57") (name "Net-(LED7-Pad1)") (class "Default")
      (node (ref "LED7") (pin "1") (pinfunction "1_1") (pintype "passive"))
      (node (ref "R20") (pin "1") (pinfunction "1_1") (pintype "passive"))
    )
    (net (code "58") (name "Net-(LED8-Pad1)") (class "Default")
      (node (ref "LED8") (pin "1") (pinfunction "1_1") (pintype "passive"))
      (node (ref "R21") (pin "1") (pinfunction "1_1") (pintype "passive"))
    )
    (net (code "59") (name "Net-(LED9-Pad1)") (class "Default")
      (node (ref "LED9") (pin "1") (pinfunction "1_1") (pintype "passive"))
      (node (ref "R23") (pin "2") (pinfunction "2_2") (pintype "passive"))
    )
    (net (code "60") (name "Net-(U2-BST)") (class "Default")
      (node (ref "C4") (pin "2") (pinfunction "2_2") (pintype "passive"))
      (node (ref "U2") (pin "8") (pinfunction "BST_8") (pintype "passive"))
    )
    (net (code "61") (name "Net-(U2-COMP)") (class "Default")
      (node (ref "C6") (pin "1") (pinfunction "1_1") (pintype "passive"))
      (node (ref "U2") (pin "3") (pinfunction "COMP_3") (pintype "passive"))
    )
    (net (code "62") (name "Net-(U2-FB)") (class "Default")
      (node (ref "R7") (pin "1") (pinfunction "1_1") (pintype "passive"))
      (node (ref "R8") (pin "1") (pinfunction "1_1") (pintype "passive"))
      (node (ref "U2") (pin "4") (pinfunction "FB_4") (pintype "passive"))
    )
    (net (code "63") (name "Net-(U2-FREQ)") (class "Default")
      (node (ref "R5") (pin "1") (pinfunction "1_1") (pintype "passive"))
      (node (ref "U2") (pin "6") (pinfunction "FREQ_6") (pintype "passive"))
    )
    (net (code "64") (name "Net-(U2-VIN)") (class "Default")
      (node (ref "C3") (pin "2") (pinfunction "2_2") (pintype "passive"))
      (node (ref "DC1") (pin "1") (pinfunction "1_1") (pintype "passive"))
      (node (ref "H1") (pin "1") (pinfunction "1_1") (pintype "passive"))
      (node (ref "U2") (pin "7") (pinfunction "VIN_7") (pintype "passive"))
    )
    (net (code "65") (name "Net-(U3-LBI)") (class "Default")
      (node (ref "R14") (pin "1") (pinfunction "1_1") (pintype "passive"))
      (node (ref "R15") (pin "1") (pinfunction "1_1") (pintype "passive"))
      (node (ref "U3") (pin "9") (pinfunction "LBI_9") (pintype "passive"))
    )
    (net (code "66") (name "Net-(U3-LBO)") (class "Default")
      (node (ref "LED3") (pin "2") (pinfunction "2_2") (pintype "passive"))
      (node (ref "U3") (pin "12") (pinfunction "LBO_12") (pintype "passive"))
    )
    (net (code "67") (name "Net-(U4-BYPASS)") (class "Default")
      (node (ref "C11") (pin "2") (pinfunction "2_2") (pintype "passive"))
      (node (ref "U4") (pin "4") (pinfunction "BYPASS_4") (pintype "passive"))
    )
    (net (code "68") (name "Net-(U4-OUT)") (class "Default")
      (node (ref "C12") (pin "1") (pinfunction "1_1") (pintype "passive"))
      (node (ref "C13") (pin "1") (pinfunction "1_1") (pintype "passive"))
      (node (ref "H2") (pin "1") (pinfunction "1_1") (pintype "passive"))
      (node (ref "H2") (pin "2") (pinfunction "2_2") (pintype "passive"))
      (node (ref "H2") (pin "3") (pinfunction "3_3") (pintype "passive"))
      (node (ref "H2") (pin "4") (pinfunction "4_4") (pintype "passive"))
      (node (ref "U4") (pin "5") (pinfunction "OUT_5") (pintype "passive"))
    )
    (net (code "69") (name "Net-(U5-PG#(TE#))") (class "Default")
      (node (ref "LED9") (pin "2") (pinfunction "2_2") (pintype "passive"))
      (node (ref "U5") (pin "7") (pinfunction "PG#(TE#)_7") (pintype "passive"))
    )
    (net (code "70") (name "Net-(U5-PROG)") (class "Default")
      (node (ref "R22") (pin "2") (pinfunction "2_2") (pintype "passive"))
      (node (ref "U5") (pin "6") (pinfunction "PROG_6") (pintype "passive"))
    )
    (net (code "71") (name "Net-(U5-STAT1)") (class "Default")
      (node (ref "LED7") (pin "2") (pinfunction "2_2") (pintype "passive"))
      (node (ref "U5") (pin "3") (pinfunction "STAT1_3") (pintype "passive"))
    )
    (net (code "72") (name "Net-(U5-STAT2)") (class "Default")
      (node (ref "LED8") (pin "2") (pinfunction "2_2") (pintype "passive"))
      (node (ref "U5") (pin "4") (pinfunction "STAT2_4") (pintype "passive"))
    )
    (net (code "73") (name "Net-(U5-THERM)") (class "Default")
      (node (ref "R24") (pin "2") (pinfunction "2_2") (pintype "passive"))
      (node (ref "U5") (pin "8") (pinfunction "THERM_8") (pintype "passive"))
    )
    (net (code "74") (name "unconnected-(DC1-Pad3)") (class "Default")
      (node (ref "DC1") (pin "3") (pinfunction "3_3") (pintype "passive+no_connect"))
    )
    (net (code "75") (name "unconnected-(U2-EN-Pad2)") (class "Default")
      (node (ref "U2") (pin "2") (pinfunction "EN_2") (pintype "passive+no_connect"))
    )
    (net (code "76") (name "unconnected-(U2-EP-Pad9)") (class "Default")
      (node (ref "U2") (pin "9") (pinfunction "EP_9") (pintype "passive+no_connect"))
    )
    (net (code "77") (name "unconnected-(U3-NC-Pad2)") (class "Default")
      (node (ref "U3") (pin "2") (pinfunction "NC_2") (pintype "passive+no_connect"))
    )
    (net (code "78") (name "unconnected-(U5-EP-Pad11)") (class "Default")
      (node (ref "U5") (pin "11") (pinfunction "EP_11") (pintype "passive+no_connect"))
    )
    (net (code "79") (name "unconnected-(USB1-CC1-PadA5)") (class "Default")
      (node (ref "USB1") (pin "A5") (pinfunction "CC1_A5") (pintype "passive+no_connect"))
    )
    (net (code "80") (name "unconnected-(USB1-CC2-PadB5)") (class "Default")
      (node (ref "USB1") (pin "B5") (pinfunction "CC2_B5") (pintype "passive+no_connect"))
    )
    (net (code "81") (name "unconnected-(USB1-D+-PadA6)") (class "Default")
      (node (ref "USB1") (pin "A6") (pinfunction "D+_A6") (pintype "passive+no_connect"))
    )
    (net (code "82") (name "unconnected-(USB1-D+-PadB6)") (class "Default")
      (node (ref "USB1") (pin "B6") (pinfunction "D+_B6") (pintype "passive+no_connect"))
    )
    (net (code "83") (name "unconnected-(USB1-D--PadA7)") (class "Default")
      (node (ref "USB1") (pin "A7") (pinfunction "D-_A7") (pintype "passive+no_connect"))
    )
    (net (code "84") (name "unconnected-(USB1-D--PadB7)") (class "Default")
      (node (ref "USB1") (pin "B7") (pinfunction "D-_B7") (pintype "passive+no_connect"))
    )
    (net (code "85") (name "unconnected-(USB1-Pad0)") (class "Default")
      (node (ref "USB1") (pin "0") (pinfunction "0_0") (pintype "passive+no_connect"))
    )
    (net (code "86") (name "unconnected-(USB1-RX1+-PadB11)") (class "Default")
      (node (ref "USB1") (pin "B11") (pinfunction "RX1+_B11") (pintype "passive+no_connect"))
    )
    (net (code "87") (name "unconnected-(USB1-RX1--PadB10)") (class "Default")
      (node (ref "USB1") (pin "B10") (pinfunction "RX1-_B10") (pintype "passive+no_connect"))
    )
    (net (code "88") (name "unconnected-(USB1-RX2+-PadA11)") (class "Default")
      (node (ref "USB1") (pin "A11") (pinfunction "RX2+_A11") (pintype "passive+no_connect"))
    )
    (net (code "89") (name "unconnected-(USB1-RX2--PadA10)") (class "Default")
      (node (ref "USB1") (pin "A10") (pinfunction "RX2-_A10") (pintype "passive+no_connect"))
    )
    (net (code "90") (name "unconnected-(USB1-SUB1-PadA8)") (class "Default")
      (node (ref "USB1") (pin "A8") (pinfunction "SUB1_A8") (pintype "passive+no_connect"))
    )
    (net (code "91") (name "unconnected-(USB1-SUB2-PadB8)") (class "Default")
      (node (ref "USB1") (pin "B8") (pinfunction "SUB2_B8") (pintype "passive+no_connect"))
    )
    (net (code "92") (name "unconnected-(USB1-TX1+-PadA2)") (class "Default")
      (node (ref "USB1") (pin "A2") (pinfunction "TX1+_A2") (pintype "passive+no_connect"))
    )
    (net (code "93") (name "unconnected-(USB1-TX1--PadA3)") (class "Default")
      (node (ref "USB1") (pin "A3") (pinfunction "TX1-_A3") (pintype "passive+no_connect"))
    )
    (net (code "94") (name "unconnected-(USB1-TX2+-PadB2)") (class "Default")
      (node (ref "USB1") (pin "B2") (pinfunction "TX2+_B2") (pintype "passive+no_connect"))
    )
    (net (code "95") (name "unconnected-(USB1-TX2--PadB3)") (class "Default")
      (node (ref "USB1") (pin "B3") (pinfunction "TX2-_B3") (pintype "passive+no_connect"))
    )
    (net (code "96") (name "unconnected-(USB2-D+-Pad3)") (class "Default")
      (node (ref "USB2") (pin "3") (pinfunction "D+_3") (pintype "passive+no_connect"))
    )
    (net (code "97") (name "unconnected-(USB2-D--Pad2)") (class "Default")
      (node (ref "USB2") (pin "2") (pinfunction "D-_2") (pintype "passive+no_connect"))
    )
    (net (code "98") (name "unconnected-(USB2-ID-Pad4)") (class "Default")
      (node (ref "USB2") (pin "4") (pinfunction "ID_4") (pintype "passive+no_connect"))
    )
    (net (code "99") (name "unconnected-(USB2-Pad6)") (class "Default")
      (node (ref "USB2") (pin "6") (pinfunction "6_6") (pintype "passive+no_connect"))
    )
  )
)
